# arduino_led_debug.net
KiCad netlist of a schematic drawn in EAGLE
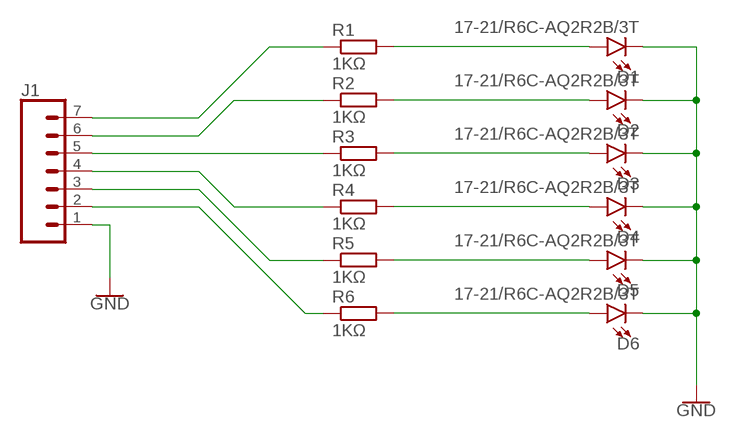
[diagram p0: schematic, sheet 1]

(export (version "E")
  (design (tool "Eeschema 10.0.6"))
  (components
    (comp (ref "D1")
      (value "17-21/R6C-AQ2R2B/3T")
      (footprint "eagle-import:LED_0805")
      (fields (field (name "LCSC_PART") "C113551"))
      (libsource (lib "eagle-import") (part "1721R6CAQ2R2B3TX_C113551_1721R6CAQ2R2B3T_0805"))
    )
    (comp (ref "D2")
      (value "17-21/R6C-AQ2R2B/3T")
      (footprint "eagle-import:LED_0805")
      (fields (field (name "LCSC_PART") "C113551"))
      (libsource (lib "eagle-import") (part "1721R6CAQ2R2B3TX_C113551_1721R6CAQ2R2B3T_0805"))
    )
    (comp (ref "D3")
      (value "17-21/R6C-AQ2R2B/3T")
      (footprint "eagle-import:LED_0805")
      (fields (field (name "LCSC_PART") "C113551"))
      (libsource (lib "eagle-import") (part "1721R6CAQ2R2B3TX_C113551_1721R6CAQ2R2B3T_0805"))
    )
    (comp (ref "D4")
      (value "17-21/R6C-AQ2R2B/3T")
      (footprint "eagle-import:LED_0805")
      (fields (field (name "LCSC_PART") "C113551"))
      (libsource (lib "eagle-import") (part "1721R6CAQ2R2B3TX_C113551_1721R6CAQ2R2B3T_0805"))
    )
    (comp (ref "D5")
      (value "17-21/R6C-AQ2R2B/3T")
      (footprint "eagle-import:LED_0805")
      (fields (field (name "LCSC_PART") "C113551"))
      (libsource (lib "eagle-import") (part "1721R6CAQ2R2B3TX_C113551_1721R6CAQ2R2B3T_0805"))
    )
    (comp (ref "D6")
      (value "17-21/R6C-AQ2R2B/3T")
      (footprint "eagle-import:LED_0805")
      (fields (field (name "LCSC_PART") "C113551"))
      (libsource (lib "eagle-import") (part "1721R6CAQ2R2B3TX_C113551_1721R6CAQ2R2B3T_0805"))
    )
    (comp (ref "J1")
      (value "CONN_07LOCK")
      (footprint "eagle-import:1X07_LOCK")
      (libsource (lib "eagle-import") (part "CONN_07LOCK"))
    )
    (comp (ref "R1")
      (value "1KΩ")
      (footprint "eagle-import:RESISTOR_0402")
      (fields (field (name "LCSC_PART") "C11702"))
      (libsource (lib "eagle-import") (part "1K_1001_1%_C11702_1K_1001_1%_0402"))
    )
    (comp (ref "R2")
      (value "1KΩ")
      (footprint "eagle-import:RESISTOR_0402")
      (fields (field (name "LCSC_PART") "C11702"))
      (libsource (lib "eagle-import") (part "1K_1001_1%_C11702_1K_1001_1%_0402"))
    )
    (comp (ref "R3")
      (value "1KΩ")
      (footprint "eagle-import:RESISTOR_0402")
      (fields (field (name "LCSC_PART") "C11702"))
      (libsource (lib "eagle-import") (part "1K_1001_1%_C11702_1K_1001_1%_0402"))
    )
    (comp (ref "R4")
      (value "1KΩ")
      (footprint "eagle-import:RESISTOR_0402")
      (fields (field (name "LCSC_PART") "C11702"))
      (libsource (lib "eagle-import") (part "1K_1001_1%_C11702_1K_1001_1%_0402"))
    )
    (comp (ref "R5")
      (value "1KΩ")
      (footprint "eagle-import:RESISTOR_0402")
      (fields (field (name "LCSC_PART") "C11702"))
      (libsource (lib "eagle-import") (part "1K_1001_1%_C11702_1K_1001_1%_0402"))
    )
    (comp (ref "R6")
      (value "1KΩ")
      (footprint "eagle-import:RESISTOR_0402")
      (fields (field (name "LCSC_PART") "C11702"))
      (libsource (lib "eagle-import") (part "1K_1001_1%_C11702_1K_1001_1%_0402"))
    )
  )
  (nets
    (net (code "1") (name "GND") (class "Default")
      (node (ref "D1") (pin "C") (pinfunction "C_C") (pintype "passive"))
      (node (ref "D2") (pin "C") (pinfunction "C_C") (pintype "passive"))
      (node (ref "D3") (pin "C") (pinfunction "C_C") (pintype "passive"))
      (node (ref "D4") (pin "C") (pinfunction "C_C") (pintype "passive"))
      (node (ref "D5") (pin "C") (pinfunction "C_C") (pintype "passive"))
      (node (ref "D6") (pin "C") (pinfunction "C_C") (pintype "passive"))
      (node (ref "J1") (pin "1") (pinfunction "1_1") (pintype "passive"))
    )
    (net (code "2") (name "Net-(R1-1)") (class "Default")
      (node (ref "J1") (pin "7") (pinfunction "7_7") (pintype "passive"))
      (node (ref "R1") (pin "2") (pinfunction "1_2") (pintype "passive"))
    )
    (net (code "3") (name "Net-(R1-2)") (class "Default")
      (node (ref "D1") (pin "A") (pinfunction "A_A") (pintype "passive"))
      (node (ref "R1") (pin "1") (pinfunction "2_1") (pintype "passive"))
    )
    (net (code "4") (name "Net-(R2-1)") (class "Default")
      (node (ref "J1") (pin "6") (pinfunction "6_6") (pintype "passive"))
      (node (ref "R2") (pin "2") (pinfunction "1_2") (pintype "passive"))
    )
    (net (code "5") (name "Net-(R2-2)") (class "Default")
      (node (ref "D2") (pin "A") (pinfunction "A_A") (pintype "passive"))
      (node (ref "R2") (pin "1") (pinfunction "2_1") (pintype "passive"))
    )
    (net (code "6") (name "Net-(R3-1)") (class "Default")
      (node (ref "J1") (pin "5") (pinfunction "5_5") (pintype "passive"))
      (node (ref "R3") (pin "2") (pinfunction "1_2") (pintype "passive"))
    )
    (net (code "7") (name "Net-(R3-2)") (class "Default")
      (node (ref "D3") (pin "A") (pinfunction "A_A") (pintype "passive"))
      (node (ref "R3") (pin "1") (pinfunction "2_1") (pintype "passive"))
    )
    (net (code "8") (name "Net-(R4-1)") (class "Default")
      (node (ref "J1") (pin "4") (pinfunction "4_4") (pintype "passive"))
      (node (ref "R4") (pin "2") (pinfunction "1_2") (pintype "passive"))
    )
    (net (code "9") (name "Net-(R4-2)") (class "Default")
      (node (ref "D4") (pin "A") (pinfunction "A_A") (pintype "passive"))
      (node (ref "R4") (pin "1") (pinfunction "2_1") (pintype "passive"))
    )
    (net (code "10") (name "Net-(R5-1)") (class "Default")
      (node (ref "J1") (pin "3") (pinfunction "3_3") (pintype "passive"))
      (node (ref "R5") (pin "2") (pinfunction "1_2") (pintype "passive"))
    )
    (net (code "11") (name "Net-(R5-2)") (class "Default")
      (node (ref "D5") (pin "A") (pinfunction "A_A") (pintype "passive"))
      (node (ref "R5") (pin "1") (pinfunction "2_1") (pintype "passive"))
    )
    (net (code "12") (name "Net-(R6-1)") (class "Default")
      (node (ref "J1") (pin "2") (pinfunction "2_2") (pintype "passive"))
      (node (ref "R6") (pin "2") (pinfunction "1_2") (pintype "passive"))
    )
    (net (code "13") (name "Net-(R6-2)") (class "Default")
      (node (ref "D6") (pin "A") (pinfunction "A_A") (pintype "passive"))
      (node (ref "R6") (pin "1") (pinfunction "2_1") (pintype "passive"))
    )
  )
)
